# SDRAM.net
KiCad netlist of a schematic drawn in Altium Designer
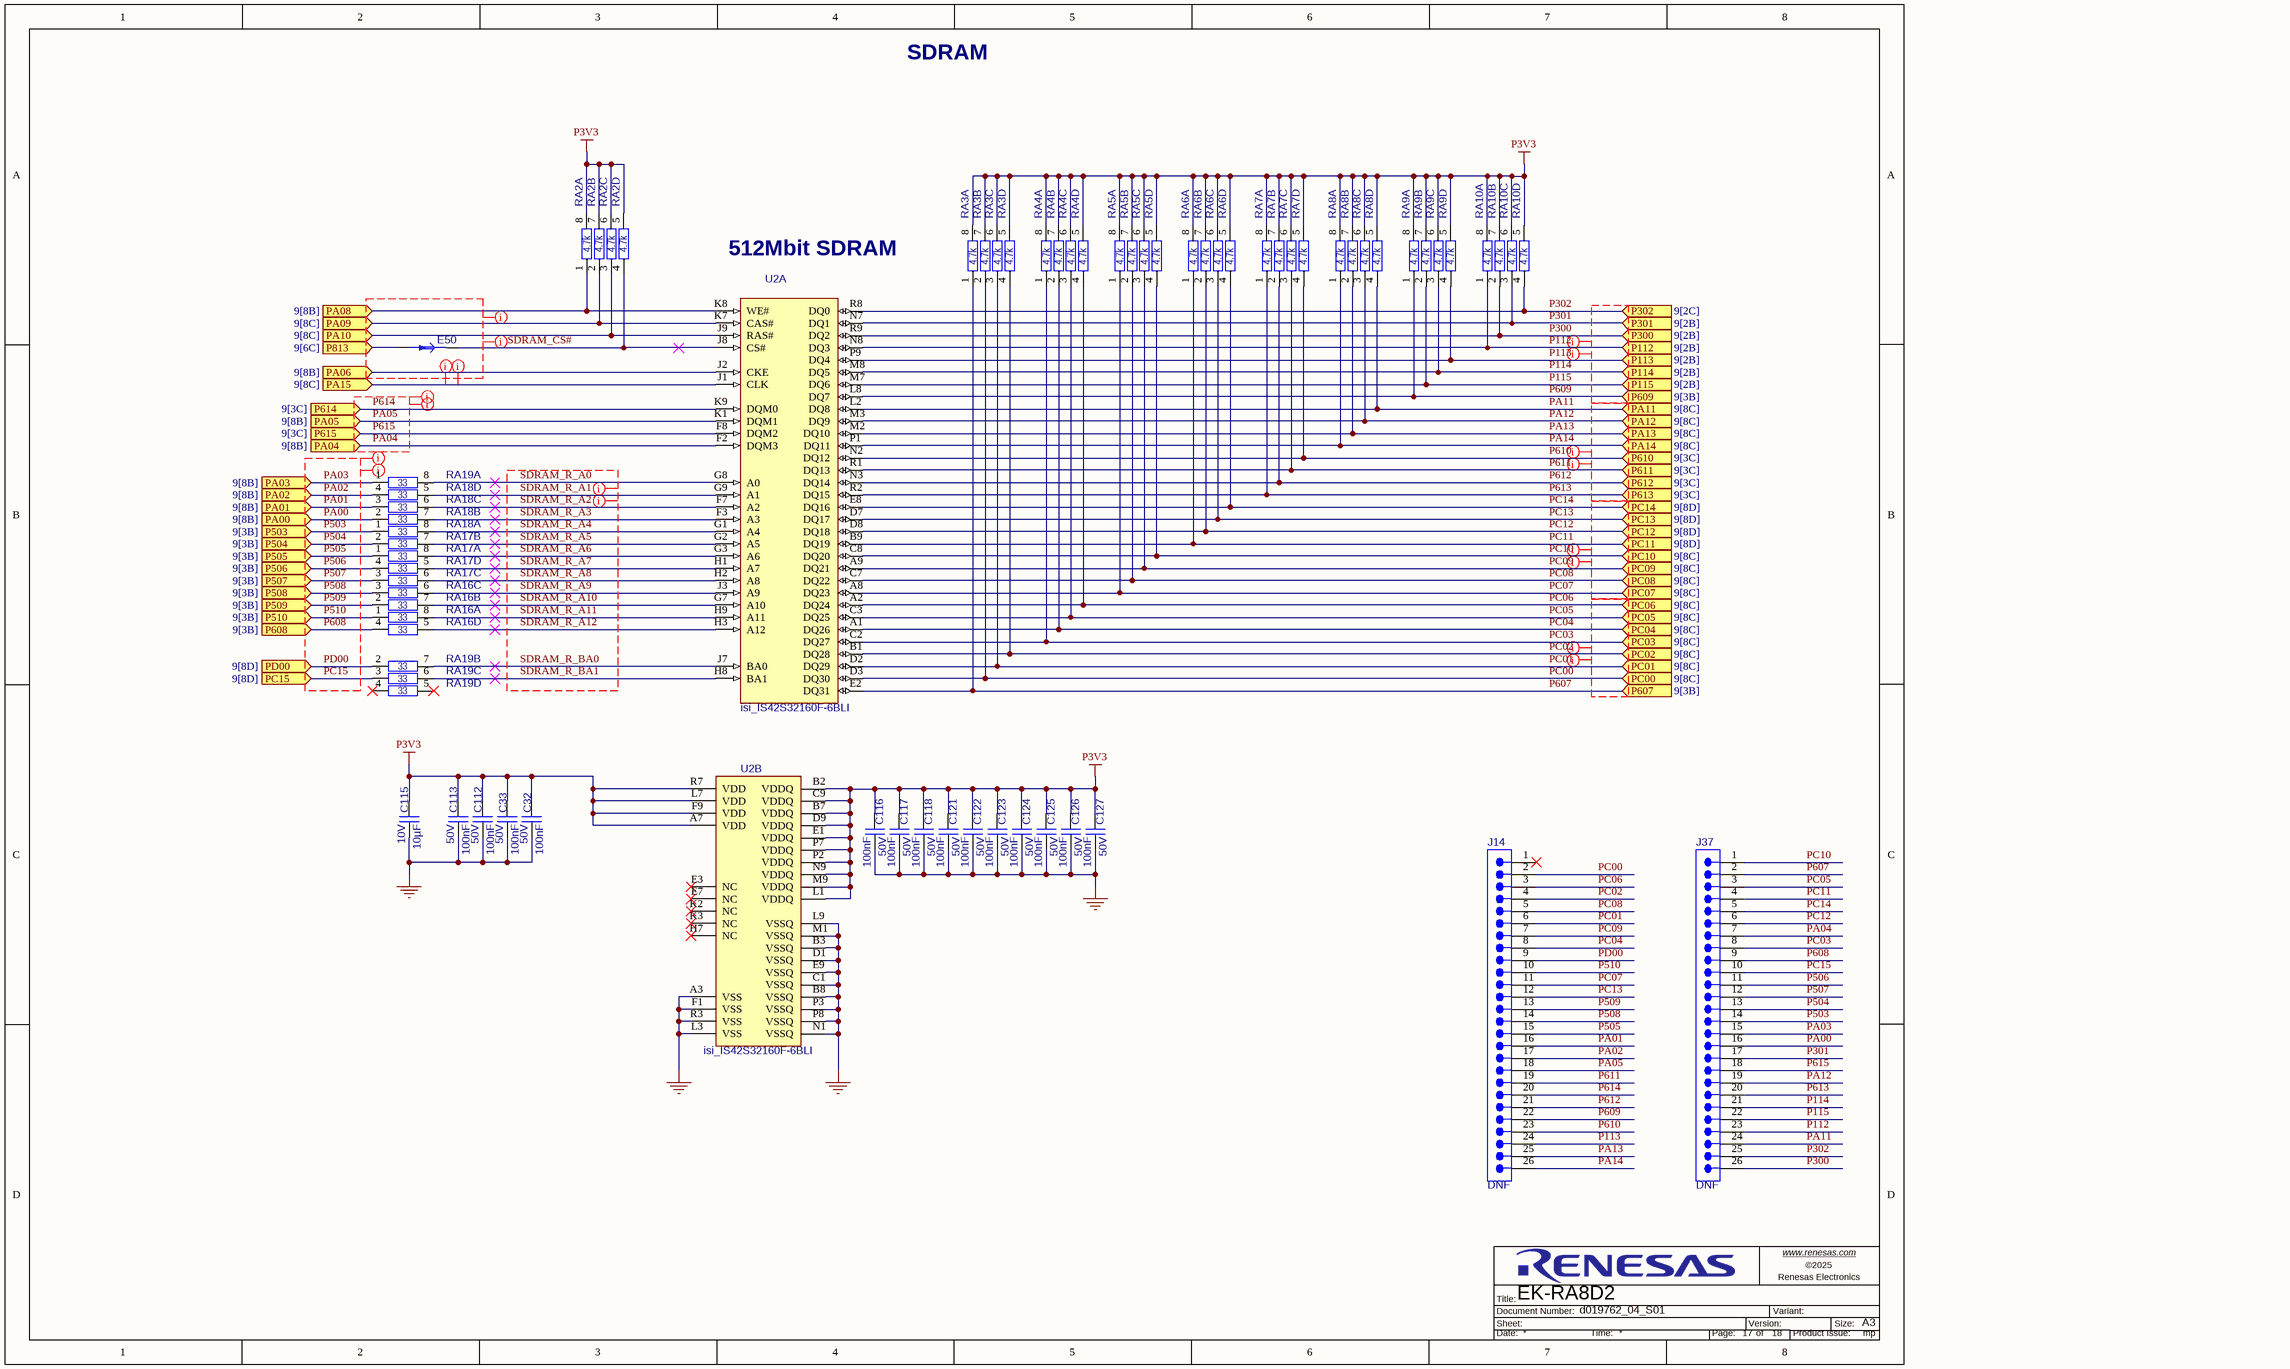
[diagram p0: SDRAM.SchDoc]

(export (version "E")
  (design (tool "Eeschema 10.0.6"))
  (components
    (comp (ref "C32")
      (value "100nF")
      (footprint "C_EIA0402_0p55")
      (description "Capacitor,EIA0402,100n,50V,X7R")
      (fields
        (field (name "TOLERANCE") "10%")
        (field (name "OPERATING VOLTAGE MAX") "50V")
        (field (name "Comment") "Capacitor")
      )
      (libsource (lib "ek-ra8d2_mp - Customer") (part "Capacitor"))
    )
    (comp (ref "C33")
      (value "100nF")
      (footprint "C_EIA0402_0p55")
      (description "Capacitor,EIA0402,100n,50V,X7R")
      (fields
        (field (name "TOLERANCE") "10%")
        (field (name "OPERATING VOLTAGE MAX") "50V")
        (field (name "Comment") "Capacitor")
      )
      (libsource (lib "ek-ra8d2_mp - Customer") (part "Capacitor"))
    )
    (comp (ref "C112")
      (value "100nF")
      (footprint "C_EIA0402_0p55")
      (description "Capacitor,EIA0402,100n,50V,X7R")
      (fields
        (field (name "TOLERANCE") "10%")
        (field (name "OPERATING VOLTAGE MAX") "50V")
        (field (name "Comment") "Capacitor")
      )
      (libsource (lib "ek-ra8d2_mp - Customer") (part "Capacitor"))
    )
    (comp (ref "C113")
      (value "100nF")
      (footprint "C_EIA0402_0p55")
      (description "Capacitor,EIA0402,100n,50V,X7R")
      (fields
        (field (name "TOLERANCE") "10%")
        (field (name "OPERATING VOLTAGE MAX") "50V")
        (field (name "Comment") "Capacitor")
      )
      (libsource (lib "ek-ra8d2_mp - Customer") (part "Capacitor"))
    )
    (comp (ref "C115")
      (value "10µF")
      (footprint "C_EIA0402_0p7")
      (description "Capacitor,EIA0402,10u,10V,X5R")
      (fields
        (field (name "TOLERANCE") "20%")
        (field (name "OPERATING VOLTAGE MAX") "10V")
        (field (name "Comment") "Capacitor")
      )
      (libsource (lib "ek-ra8d2_mp - Customer") (part "Capacitor"))
    )
    (comp (ref "C116")
      (value "100nF")
      (footprint "C_EIA0402_0p55")
      (description "Capacitor,EIA0402,100n,50V,X7R")
      (fields
        (field (name "TOLERANCE") "10%")
        (field (name "OPERATING VOLTAGE MAX") "50V")
        (field (name "Comment") "Capacitor")
      )
      (libsource (lib "ek-ra8d2_mp - Customer") (part "Capacitor"))
    )
    (comp (ref "C117")
      (value "100nF")
      (footprint "C_EIA0402_0p55")
      (description "Capacitor,EIA0402,100n,50V,X7R")
      (fields
        (field (name "TOLERANCE") "10%")
        (field (name "OPERATING VOLTAGE MAX") "50V")
        (field (name "Comment") "Capacitor")
      )
      (libsource (lib "ek-ra8d2_mp - Customer") (part "Capacitor"))
    )
    (comp (ref "C118")
      (value "100nF")
      (footprint "C_EIA0402_0p55")
      (description "Capacitor,EIA0402,100n,50V,X7R")
      (fields
        (field (name "TOLERANCE") "10%")
        (field (name "OPERATING VOLTAGE MAX") "50V")
        (field (name "Comment") "Capacitor")
      )
      (libsource (lib "ek-ra8d2_mp - Customer") (part "Capacitor"))
    )
    (comp (ref "C121")
      (value "100nF")
      (footprint "C_EIA0402_0p55")
      (description "Capacitor,EIA0402,100n,50V,X7R")
      (fields
        (field (name "TOLERANCE") "10%")
        (field (name "OPERATING VOLTAGE MAX") "50V")
        (field (name "Comment") "Capacitor")
      )
      (libsource (lib "ek-ra8d2_mp - Customer") (part "Capacitor"))
    )
    (comp (ref "C122")
      (value "100nF")
      (footprint "C_EIA0402_0p55")
      (description "Capacitor,EIA0402,100n,50V,X7R")
      (fields
        (field (name "TOLERANCE") "10%")
        (field (name "OPERATING VOLTAGE MAX") "50V")
        (field (name "Comment") "Capacitor")
      )
      (libsource (lib "ek-ra8d2_mp - Customer") (part "Capacitor"))
    )
    (comp (ref "C123")
      (value "100nF")
      (footprint "C_EIA0402_0p55")
      (description "Capacitor,EIA0402,100n,50V,X7R")
      (fields
        (field (name "TOLERANCE") "10%")
        (field (name "OPERATING VOLTAGE MAX") "50V")
        (field (name "Comment") "Capacitor")
      )
      (libsource (lib "ek-ra8d2_mp - Customer") (part "Capacitor"))
    )
    (comp (ref "C124")
      (value "100nF")
      (footprint "C_EIA0402_0p55")
      (description "Capacitor,EIA0402,100n,50V,X7R")
      (fields
        (field (name "TOLERANCE") "10%")
        (field (name "OPERATING VOLTAGE MAX") "50V")
        (field (name "Comment") "Capacitor")
      )
      (libsource (lib "ek-ra8d2_mp - Customer") (part "Capacitor"))
    )
    (comp (ref "C125")
      (value "100nF")
      (footprint "C_EIA0402_0p55")
      (description "Capacitor,EIA0402,100n,50V,X7R")
      (fields
        (field (name "TOLERANCE") "10%")
        (field (name "OPERATING VOLTAGE MAX") "50V")
        (field (name "Comment") "Capacitor")
      )
      (libsource (lib "ek-ra8d2_mp - Customer") (part "Capacitor"))
    )
    (comp (ref "C126")
      (value "100nF")
      (footprint "C_EIA0402_0p55")
      (description "Capacitor,EIA0402,100n,50V,X7R")
      (fields
        (field (name "TOLERANCE") "10%")
        (field (name "OPERATING VOLTAGE MAX") "50V")
        (field (name "Comment") "Capacitor")
      )
      (libsource (lib "ek-ra8d2_mp - Customer") (part "Capacitor"))
    )
    (comp (ref "C127")
      (value "100nF")
      (footprint "C_EIA0402_0p55")
      (description "Capacitor,EIA0402,100n,50V,X7R")
      (fields
        (field (name "TOLERANCE") "10%")
        (field (name "OPERATING VOLTAGE MAX") "50V")
        (field (name "Comment") "Capacitor")
      )
      (libsource (lib "ek-ra8d2_mp - Customer") (part "Capacitor"))
    )
    (comp (ref "E50")
      (value "TRACE_CUT_0805")
      (footprint "trace_cut_0805")
      (description "Trace Cut, SMD, 0805 size")
      (libsource (lib "ek-ra8d2_mp - Customer") (part "trace_cut"))
    )
    (comp (ref "J14")
      (value "NRPN132PAEN-RC")
      (footprint "sul_NRPN132PAEN-RC")
      (description "Header,26way,2row,vertical,2.00mm,THT")
      (fields (field (name "DNF") "DNF"))
      (libsource (lib "ek-ra8d2_mp - Customer") (part "CON_026"))
    )
    (comp (ref "J37")
      (value "NRPN132PAEN-RC")
      (footprint "sul_NRPN132PAEN-RC")
      (description "Header,26way,2row,vertical,2.00mm,THT")
      (fields (field (name "DNF") "DNF"))
      (libsource (lib "ek-ra8d2_mp - Customer") (part "CON_026"))
    )
    (comp (ref "RA2")
      (value "4.7k")
      (footprint "R_Array_EIA0804")
      (description "Resistor Network & Array,0804,4.7k,0.0625W")
      (fields (field (name "POWER") "62.5mW") (field (name "TOLERANCE") "1%"))
      (libsource (lib "") (part "Resistor_Array_1"))
    )
    (comp (ref "RA3")
      (value "4.7k")
      (footprint "R_Array_EIA0804")
      (description "Resistor Network & Array,0804,4.7k,0.0625W")
      (fields (field (name "POWER") "62.5mW") (field (name "TOLERANCE") "1%"))
      (libsource (lib "") (part "Resistor_Array_1"))
    )
    (comp (ref "RA4")
      (value "4.7k")
      (footprint "R_Array_EIA0804")
      (description "Resistor Network & Array,0804,4.7k,0.0625W")
      (fields (field (name "POWER") "62.5mW") (field (name "TOLERANCE") "1%"))
      (libsource (lib "") (part "Resistor_Array_1"))
    )
    (comp (ref "RA5")
      (value "4.7k")
      (footprint "R_Array_EIA0804")
      (description "Resistor Network & Array,0804,4.7k,0.0625W")
      (fields (field (name "POWER") "62.5mW") (field (name "TOLERANCE") "1%"))
      (libsource (lib "") (part "Resistor_Array_1"))
    )
    (comp (ref "RA6")
      (value "4.7k")
      (footprint "R_Array_EIA0804")
      (description "Resistor Network & Array,0804,4.7k,0.0625W")
      (fields (field (name "POWER") "62.5mW") (field (name "TOLERANCE") "1%"))
      (libsource (lib "") (part "Resistor_Array_1"))
    )
    (comp (ref "RA7")
      (value "4.7k")
      (footprint "R_Array_EIA0804")
      (description "Resistor Network & Array,0804,4.7k,0.0625W")
      (fields (field (name "POWER") "62.5mW") (field (name "TOLERANCE") "1%"))
      (libsource (lib "") (part "Resistor_Array_1"))
    )
    (comp (ref "RA8")
      (value "4.7k")
      (footprint "R_Array_EIA0804")
      (description "Resistor Network & Array,0804,4.7k,0.0625W")
      (fields (field (name "POWER") "62.5mW") (field (name "TOLERANCE") "1%"))
      (libsource (lib "") (part "Resistor_Array_1"))
    )
    (comp (ref "RA9")
      (value "4.7k")
      (footprint "R_Array_EIA0804")
      (description "Resistor Network & Array,0804,4.7k,0.0625W")
      (fields (field (name "POWER") "62.5mW") (field (name "TOLERANCE") "1%"))
      (libsource (lib "") (part "Resistor_Array_1"))
    )
    (comp (ref "RA10")
      (value "4.7k")
      (footprint "R_Array_EIA0804")
      (description "Resistor Network & Array,0804,4.7k,0.0625W")
      (fields (field (name "POWER") "62.5mW") (field (name "TOLERANCE") "1%"))
      (libsource (lib "") (part "Resistor_Array_1"))
    )
    (comp (ref "RA16")
      (value "33")
      (footprint "R_Array_EIA0804")
      (description "Resistor Network & Array,0804,33,0.0625W")
      (fields (field (name "POWER") "62.5mW") (field (name "TOLERANCE") "1%"))
      (libsource (lib "ek-ra8d2_mp - Customer") (part "Resistor_Array"))
    )
    (comp (ref "RA17")
      (value "33")
      (footprint "R_Array_EIA0804")
      (description "Resistor Network & Array,0804,33,0.0625W")
      (fields (field (name "POWER") "62.5mW") (field (name "TOLERANCE") "1%"))
      (libsource (lib "ek-ra8d2_mp - Customer") (part "Resistor_Array"))
    )
    (comp (ref "RA18")
      (value "33")
      (footprint "R_Array_EIA0804")
      (description "Resistor Network & Array,0804,33,0.0625W")
      (fields (field (name "POWER") "62.5mW") (field (name "TOLERANCE") "1%"))
      (libsource (lib "ek-ra8d2_mp - Customer") (part "Resistor_Array"))
    )
    (comp (ref "RA19")
      (value "33")
      (footprint "R_Array_EIA0804")
      (description "Resistor Network & Array,0804,33,0.0625W")
      (fields (field (name "POWER") "62.5mW") (field (name "TOLERANCE") "1%"))
      (libsource (lib "ek-ra8d2_mp - Customer") (part "Resistor_Array"))
    )
    (comp (ref "U2")
      (value "isi_IS42S32160F-6BLI")
      (footprint "isi_TF-BGA-90_8x13mm")
      (description "512Mb Synchronous DRAM, 16MX32, 5.4ns, CMOS, TF-BGA90")
      (libsource (lib "ek-ra8d2_mp - Customer") (part "isi_IS42S32160F-6BLI"))
    )
  )
  (nets
    (net (code "2") (name "/P112") (class "Default")
      (node (ref "J37") (pin "23") (pinfunction "23_23") (pintype "passive"))
      (node (ref "RA10") (pin "1") (pinfunction "1_1") (pintype "passive"))
      (node (ref "U2") (pin "N8") (pinfunction "DQ3_N8") (pintype "bidirectional"))
    )
    (net (code "3") (name "/P113") (class "Default")
      (node (ref "J14") (pin "24") (pinfunction "24_24") (pintype "passive"))
      (node (ref "RA9") (pin "4") (pinfunction "4_4") (pintype "passive"))
      (node (ref "U2") (pin "P9") (pinfunction "DQ4_P9") (pintype "bidirectional"))
    )
    (net (code "4") (name "/P114") (class "Default")
      (node (ref "J37") (pin "21") (pinfunction "21_21") (pintype "passive"))
      (node (ref "RA9") (pin "3") (pinfunction "3_3") (pintype "passive"))
      (node (ref "U2") (pin "M8") (pinfunction "DQ5_M8") (pintype "bidirectional"))
    )
    (net (code "5") (name "/P115") (class "Default")
      (node (ref "J37") (pin "22") (pinfunction "22_22") (pintype "passive"))
      (node (ref "RA9") (pin "2") (pinfunction "2_2") (pintype "passive"))
      (node (ref "U2") (pin "M7") (pinfunction "DQ6_M7") (pintype "bidirectional"))
    )
    (net (code "6") (name "/P300") (class "Default")
      (node (ref "J37") (pin "26") (pinfunction "26_26") (pintype "passive"))
      (node (ref "RA10") (pin "2") (pinfunction "2_2") (pintype "passive"))
      (node (ref "U2") (pin "R9") (pinfunction "DQ2_R9") (pintype "bidirectional"))
    )
    (net (code "7") (name "/P301") (class "Default")
      (node (ref "J37") (pin "17") (pinfunction "17_17") (pintype "passive"))
      (node (ref "RA10") (pin "3") (pinfunction "3_3") (pintype "passive"))
      (node (ref "U2") (pin "N7") (pinfunction "DQ1_N7") (pintype "bidirectional"))
    )
    (net (code "8") (name "/P302") (class "Default")
      (node (ref "J37") (pin "25") (pinfunction "25_25") (pintype "passive"))
      (node (ref "RA10") (pin "4") (pinfunction "4_4") (pintype "passive"))
      (node (ref "U2") (pin "R8") (pinfunction "DQ0_R8") (pintype "bidirectional"))
    )
    (net (code "9") (name "/P503") (class "Default")
      (node (ref "J37") (pin "14") (pinfunction "14_14") (pintype "passive"))
      (node (ref "RA18") (pin "1") (pinfunction "1_1") (pintype "passive"))
    )
    (net (code "10") (name "/P504") (class "Default")
      (node (ref "J37") (pin "13") (pinfunction "13_13") (pintype "passive"))
      (node (ref "RA17") (pin "2") (pinfunction "2_2") (pintype "passive"))
    )
    (net (code "11") (name "/P505") (class "Default")
      (node (ref "J14") (pin "15") (pinfunction "15_15") (pintype "passive"))
      (node (ref "RA17") (pin "1") (pinfunction "1_1") (pintype "passive"))
    )
    (net (code "12") (name "/P506") (class "Default")
      (node (ref "J37") (pin "11") (pinfunction "11_11") (pintype "passive"))
      (node (ref "RA17") (pin "4") (pinfunction "4_4") (pintype "passive"))
    )
    (net (code "13") (name "/P507") (class "Default")
      (node (ref "J37") (pin "12") (pinfunction "12_12") (pintype "passive"))
      (node (ref "RA17") (pin "3") (pinfunction "3_3") (pintype "passive"))
    )
    (net (code "14") (name "/P508") (class "Default")
      (node (ref "J14") (pin "14") (pinfunction "14_14") (pintype "passive"))
      (node (ref "RA16") (pin "3") (pinfunction "3_3") (pintype "passive"))
    )
    (net (code "15") (name "/P509") (class "Default")
      (node (ref "J14") (pin "13") (pinfunction "13_13") (pintype "passive"))
      (node (ref "RA16") (pin "2") (pinfunction "2_2") (pintype "passive"))
    )
    (net (code "16") (name "/P510") (class "Default")
      (node (ref "J14") (pin "10") (pinfunction "10_10") (pintype "passive"))
      (node (ref "RA16") (pin "1") (pinfunction "1_1") (pintype "passive"))
    )
    (net (code "17") (name "/P607") (class "Default")
      (node (ref "J37") (pin "2") (pinfunction "2_2") (pintype "passive"))
      (node (ref "RA3") (pin "1") (pinfunction "1_1") (pintype "passive"))
      (node (ref "U2") (pin "E2") (pinfunction "DQ31_E2") (pintype "bidirectional"))
    )
    (net (code "18") (name "/P608") (class "Default")
      (node (ref "J37") (pin "9") (pinfunction "9_9") (pintype "passive"))
      (node (ref "RA16") (pin "4") (pinfunction "4_4") (pintype "passive"))
    )
    (net (code "19") (name "/P609") (class "Default")
      (node (ref "J14") (pin "22") (pinfunction "22_22") (pintype "passive"))
      (node (ref "RA9") (pin "1") (pinfunction "1_1") (pintype "passive"))
      (node (ref "U2") (pin "L8") (pinfunction "DQ7_L8") (pintype "bidirectional"))
    )
    (net (code "20") (name "/P610") (class "Default")
      (node (ref "J14") (pin "23") (pinfunction "23_23") (pintype "passive"))
      (node (ref "RA7") (pin "4") (pinfunction "4_4") (pintype "passive"))
      (node (ref "U2") (pin "N2") (pinfunction "DQ12_N2") (pintype "bidirectional"))
    )
    (net (code "21") (name "/P611") (class "Default")
      (node (ref "J14") (pin "19") (pinfunction "19_19") (pintype "passive"))
      (node (ref "RA7") (pin "3") (pinfunction "3_3") (pintype "passive"))
      (node (ref "U2") (pin "R1") (pinfunction "DQ13_R1") (pintype "bidirectional"))
    )
    (net (code "22") (name "/P612") (class "Default")
      (node (ref "J14") (pin "21") (pinfunction "21_21") (pintype "passive"))
      (node (ref "RA7") (pin "2") (pinfunction "2_2") (pintype "passive"))
      (node (ref "U2") (pin "N3") (pinfunction "DQ14_N3") (pintype "bidirectional"))
    )
    (net (code "23") (name "/P613") (class "Default")
      (node (ref "J37") (pin "20") (pinfunction "20_20") (pintype "passive"))
      (node (ref "RA7") (pin "1") (pinfunction "1_1") (pintype "passive"))
      (node (ref "U2") (pin "R2") (pinfunction "DQ15_R2") (pintype "bidirectional"))
    )
    (net (code "24") (name "/P614") (class "Default")
      (node (ref "J14") (pin "20") (pinfunction "20_20") (pintype "passive"))
      (node (ref "U2") (pin "K9") (pinfunction "DQM0_K9") (pintype "input"))
    )
    (net (code "25") (name "/P615") (class "Default")
      (node (ref "J37") (pin "18") (pinfunction "18_18") (pintype "passive"))
      (node (ref "U2") (pin "F8") (pinfunction "DQM2_F8") (pintype "input"))
    )
    (net (code "26") (name "/P813") (class "Default")
      (node (ref "E50") (pin "2") (pinfunction "2_2") (pintype "passive"))
    )
    (net (code "27") (name "/PA00") (class "Default")
      (node (ref "J37") (pin "16") (pinfunction "16_16") (pintype "passive"))
      (node (ref "RA18") (pin "2") (pinfunction "2_2") (pintype "passive"))
    )
    (net (code "28") (name "/PA01") (class "Default")
      (node (ref "J14") (pin "16") (pinfunction "16_16") (pintype "passive"))
      (node (ref "RA18") (pin "3") (pinfunction "3_3") (pintype "passive"))
    )
    (net (code "29") (name "/PA02") (class "Default")
      (node (ref "J14") (pin "17") (pinfunction "17_17") (pintype "passive"))
      (node (ref "RA18") (pin "4") (pinfunction "4_4") (pintype "passive"))
    )
    (net (code "30") (name "/PA03") (class "Default")
      (node (ref "J37") (pin "15") (pinfunction "15_15") (pintype "passive"))
      (node (ref "RA19") (pin "1") (pinfunction "1_1") (pintype "passive"))
    )
    (net (code "31") (name "/PA04") (class "Default")
      (node (ref "J37") (pin "7") (pinfunction "7_7") (pintype "passive"))
      (node (ref "U2") (pin "F2") (pinfunction "DQM3_F2") (pintype "input"))
    )
    (net (code "32") (name "/PA05") (class "Default")
      (node (ref "J14") (pin "18") (pinfunction "18_18") (pintype "passive"))
      (node (ref "U2") (pin "K1") (pinfunction "DQM1_K1") (pintype "input"))
    )
    (net (code "33") (name "/PA06") (class "Default")
      (node (ref "U2") (pin "J2") (pinfunction "CKE_J2") (pintype "input"))
    )
    (net (code "34") (name "/PA08") (class "Default")
      (node (ref "RA2") (pin "1") (pinfunction "1_1") (pintype "passive"))
      (node (ref "U2") (pin "K8") (pinfunction "WE#_K8") (pintype "input"))
    )
    (net (code "35") (name "/PA09") (class "Default")
      (node (ref "RA2") (pin "2") (pinfunction "2_2") (pintype "passive"))
      (node (ref "U2") (pin "K7") (pinfunction "CAS#_K7") (pintype "input"))
    )
    (net (code "36") (name "/PA10") (class "Default")
      (node (ref "RA2") (pin "3") (pinfunction "3_3") (pintype "passive"))
      (node (ref "U2") (pin "J9") (pinfunction "RAS#_J9") (pintype "input"))
    )
    (net (code "37") (name "/PA11") (class "Default")
      (node (ref "J37") (pin "24") (pinfunction "24_24") (pintype "passive"))
      (node (ref "RA8") (pin "4") (pinfunction "4_4") (pintype "passive"))
      (node (ref "U2") (pin "L2") (pinfunction "DQ8_L2") (pintype "bidirectional"))
    )
    (net (code "38") (name "/PA12") (class "Default")
      (node (ref "J37") (pin "19") (pinfunction "19_19") (pintype "passive"))
      (node (ref "RA8") (pin "3") (pinfunction "3_3") (pintype "passive"))
      (node (ref "U2") (pin "M3") (pinfunction "DQ9_M3") (pintype "bidirectional"))
    )
    (net (code "39") (name "/PA13") (class "Default")
      (node (ref "J14") (pin "25") (pinfunction "25_25") (pintype "passive"))
      (node (ref "RA8") (pin "2") (pinfunction "2_2") (pintype "passive"))
      (node (ref "U2") (pin "M2") (pinfunction "DQ10_M2") (pintype "bidirectional"))
    )
    (net (code "40") (name "/PA14") (class "Default")
      (node (ref "J14") (pin "26") (pinfunction "26_26") (pintype "passive"))
      (node (ref "RA8") (pin "1") (pinfunction "1_1") (pintype "passive"))
      (node (ref "U2") (pin "P1") (pinfunction "DQ11_P1") (pintype "bidirectional"))
    )
    (net (code "41") (name "/PA15") (class "Default")
      (node (ref "U2") (pin "J1") (pinfunction "CLK_J1") (pintype "input"))
    )
    (net (code "42") (name "/PC00") (class "Default")
      (node (ref "J14") (pin "2") (pinfunction "2_2") (pintype "passive"))
      (node (ref "RA3") (pin "2") (pinfunction "2_2") (pintype "passive"))
      (node (ref "U2") (pin "D3") (pinfunction "DQ30_D3") (pintype "bidirectional"))
    )
    (net (code "43") (name "/PC01") (class "Default")
      (node (ref "J14") (pin "6") (pinfunction "6_6") (pintype "passive"))
      (node (ref "RA3") (pin "3") (pinfunction "3_3") (pintype "passive"))
      (node (ref "U2") (pin "D2") (pinfunction "DQ29_D2") (pintype "bidirectional"))
    )
    (net (code "44") (name "/PC02") (class "Default")
      (node (ref "J14") (pin "4") (pinfunction "4_4") (pintype "passive"))
      (node (ref "RA3") (pin "4") (pinfunction "4_4") (pintype "passive"))
      (node (ref "U2") (pin "B1") (pinfunction "DQ28_B1") (pintype "bidirectional"))
    )
    (net (code "45") (name "/PC03") (class "Default")
      (node (ref "J37") (pin "8") (pinfunction "8_8") (pintype "passive"))
      (node (ref "RA4") (pin "1") (pinfunction "1_1") (pintype "passive"))
      (node (ref "U2") (pin "C2") (pinfunction "DQ27_C2") (pintype "bidirectional"))
    )
    (net (code "46") (name "/PC04") (class "Default")
      (node (ref "J14") (pin "8") (pinfunction "8_8") (pintype "passive"))
      (node (ref "RA4") (pin "2") (pinfunction "2_2") (pintype "passive"))
      (node (ref "U2") (pin "A1") (pinfunction "DQ26_A1") (pintype "bidirectional"))
    )
    (net (code "47") (name "/PC05") (class "Default")
      (node (ref "J37") (pin "3") (pinfunction "3_3") (pintype "passive"))
      (node (ref "RA4") (pin "3") (pinfunction "3_3") (pintype "passive"))
      (node (ref "U2") (pin "C3") (pinfunction "DQ25_C3") (pintype "bidirectional"))
    )
    (net (code "48") (name "/PC06") (class "Default")
      (node (ref "J14") (pin "3") (pinfunction "3_3") (pintype "passive"))
      (node (ref "RA4") (pin "4") (pinfunction "4_4") (pintype "passive"))
      (node (ref "U2") (pin "A2") (pinfunction "DQ24_A2") (pintype "bidirectional"))
    )
    (net (code "49") (name "/PC07") (class "Default")
      (node (ref "J14") (pin "11") (pinfunction "11_11") (pintype "passive"))
      (node (ref "RA5") (pin "1") (pinfunction "1_1") (pintype "passive"))
      (node (ref "U2") (pin "A8") (pinfunction "DQ23_A8") (pintype "bidirectional"))
    )
    (net (code "50") (name "/PC08") (class "Default")
      (node (ref "J14") (pin "5") (pinfunction "5_5") (pintype "passive"))
      (node (ref "RA5") (pin "2") (pinfunction "2_2") (pintype "passive"))
      (node (ref "U2") (pin "C7") (pinfunction "DQ22_C7") (pintype "bidirectional"))
    )
    (net (code "51") (name "/PC09") (class "Default")
      (node (ref "J14") (pin "7") (pinfunction "7_7") (pintype "passive"))
      (node (ref "RA5") (pin "3") (pinfunction "3_3") (pintype "passive"))
      (node (ref "U2") (pin "A9") (pinfunction "DQ21_A9") (pintype "bidirectional"))
    )
    (net (code "52") (name "/PC10") (class "Default")
      (node (ref "J37") (pin "1") (pinfunction "1_1") (pintype "passive"))
      (node (ref "RA5") (pin "4") (pinfunction "4_4") (pintype "passive"))
      (node (ref "U2") (pin "C8") (pinfunction "DQ20_C8") (pintype "bidirectional"))
    )
    (net (code "53") (name "/PC11") (class "Default")
      (node (ref "J37") (pin "4") (pinfunction "4_4") (pintype "passive"))
      (node (ref "RA6") (pin "1") (pinfunction "1_1") (pintype "passive"))
      (node (ref "U2") (pin "B9") (pinfunction "DQ19_B9") (pintype "bidirectional"))
    )
    (net (code "54") (name "/PC12") (class "Default")
      (node (ref "J37") (pin "6") (pinfunction "6_6") (pintype "passive"))
      (node (ref "RA6") (pin "2") (pinfunction "2_2") (pintype "passive"))
      (node (ref "U2") (pin "D8") (pinfunction "DQ18_D8") (pintype "bidirectional"))
    )
    (net (code "55") (name "/PC13") (class "Default")
      (node (ref "J14") (pin "12") (pinfunction "12_12") (pintype "passive"))
      (node (ref "RA6") (pin "3") (pinfunction "3_3") (pintype "passive"))
      (node (ref "U2") (pin "D7") (pinfunction "DQ17_D7") (pintype "bidirectional"))
    )
    (net (code "56") (name "/PC14") (class "Default")
      (node (ref "J37") (pin "5") (pinfunction "5_5") (pintype "passive"))
      (node (ref "RA6") (pin "4") (pinfunction "4_4") (pintype "passive"))
      (node (ref "U2") (pin "E8") (pinfunction "DQ16_E8") (pintype "bidirectional"))
    )
    (net (code "57") (name "/PC15") (class "Default")
      (node (ref "J37") (pin "10") (pinfunction "10_10") (pintype "passive"))
      (node (ref "RA19") (pin "3") (pinfunction "3_3") (pintype "passive"))
    )
    (net (code "58") (name "/PD00") (class "Default")
      (node (ref "J14") (pin "9") (pinfunction "9_9") (pintype "passive"))
      (node (ref "RA19") (pin "2") (pinfunction "2_2") (pintype "passive"))
    )
    (net (code "59") (name "/SDRAM_CS#") (class "Default")
      (node (ref "E50") (pin "1") (pinfunction "1_1") (pintype "passive"))
      (node (ref "RA2") (pin "4") (pinfunction "4_4") (pintype "passive"))
      (node (ref "U2") (pin "J8") (pinfunction "CS#_J8") (pintype "input"))
    )
    (net (code "60") (name "/SDRAM_R_A0") (class "Default")
      (node (ref "RA19") (pin "8") (pinfunction "8_8") (pintype "passive"))
      (node (ref "U2") (pin "G8") (pinfunction "A0_G8") (pintype "input"))
    )
    (net (code "61") (name "/SDRAM_R_A1") (class "Default")
      (node (ref "RA18") (pin "5") (pinfunction "5_5") (pintype "passive"))
      (node (ref "U2") (pin "G9") (pinfunction "A1_G9") (pintype "input"))
    )
    (net (code "62") (name "/SDRAM_R_A2") (class "Default")
      (node (ref "RA18") (pin "6") (pinfunction "6_6") (pintype "passive"))
      (node (ref "U2") (pin "F7") (pinfunction "A2_F7") (pintype "input"))
    )
    (net (code "63") (name "/SDRAM_R_A3") (class "Default")
      (node (ref "RA18") (pin "7") (pinfunction "7_7") (pintype "passive"))
      (node (ref "U2") (pin "F3") (pinfunction "A3_F3") (pintype "input"))
    )
    (net (code "64") (name "/SDRAM_R_A4") (class "Default")
      (node (ref "RA18") (pin "8") (pinfunction "8_8") (pintype "passive"))
      (node (ref "U2") (pin "G1") (pinfunction "A4_G1") (pintype "input"))
    )
    (net (code "65") (name "/SDRAM_R_A5") (class "Default")
      (node (ref "RA17") (pin "7") (pinfunction "7_7") (pintype "passive"))
      (node (ref "U2") (pin "G2") (pinfunction "A5_G2") (pintype "input"))
    )
    (net (code "66") (name "/SDRAM_R_A6") (class "Default")
      (node (ref "RA17") (pin "8") (pinfunction "8_8") (pintype "passive"))
      (node (ref "U2") (pin "G3") (pinfunction "A6_G3") (pintype "input"))
    )
    (net (code "67") (name "/SDRAM_R_A7") (class "Default")
      (node (ref "RA17") (pin "5") (pinfunction "5_5") (pintype "passive"))
      (node (ref "U2") (pin "H1") (pinfunction "A7_H1") (pintype "input"))
    )
    (net (code "68") (name "/SDRAM_R_A8") (class "Default")
      (node (ref "RA17") (pin "6") (pinfunction "6_6") (pintype "passive"))
      (node (ref "U2") (pin "H2") (pinfunction "A8_H2") (pintype "input"))
    )
    (net (code "69") (name "/SDRAM_R_A9") (class "Default")
      (node (ref "RA16") (pin "6") (pinfunction "6_6") (pintype "passive"))
      (node (ref "U2") (pin "J3") (pinfunction "A9_J3") (pintype "input"))
    )
    (net (code "70") (name "/SDRAM_R_A10") (class "Default")
      (node (ref "RA16") (pin "7") (pinfunction "7_7") (pintype "passive"))
      (node (ref "U2") (pin "G7") (pinfunction "A10_G7") (pintype "input"))
    )
    (net (code "71") (name "/SDRAM_R_A11") (class "Default")
      (node (ref "RA16") (pin "8") (pinfunction "8_8") (pintype "passive"))
      (node (ref "U2") (pin "H9") (pinfunction "A11_H9") (pintype "input"))
    )
    (net (code "72") (name "/SDRAM_R_A12") (class "Default")
      (node (ref "RA16") (pin "5") (pinfunction "5_5") (pintype "passive"))
      (node (ref "U2") (pin "H3") (pinfunction "A12_H3") (pintype "input"))
    )
    (net (code "73") (name "/SDRAM_R_BA0") (class "Default")
      (node (ref "RA19") (pin "7") (pinfunction "7_7") (pintype "passive"))
      (node (ref "U2") (pin "J7") (pinfunction "BA0_J7") (pintype "input"))
    )
    (net (code "74") (name "/SDRAM_R_BA1") (class "Default")
      (node (ref "RA19") (pin "6") (pinfunction "6_6") (pintype "passive"))
      (node (ref "U2") (pin "H8") (pinfunction "BA1_H8") (pintype "input"))
    )
    (net (code "75") (name "GND") (class "Default")
      (node (ref "C112") (pin "2") (pinfunction "2_2") (pintype "passive"))
      (node (ref "C113") (pin "2") (pinfunction "2_2") (pintype "passive"))
      (node (ref "C115") (pin "2") (pinfunction "2_2") (pintype "passive"))
      (node (ref "C116") (pin "2") (pinfunction "2_2") (pintype "passive"))
      (node (ref "C117") (pin "2") (pinfunction "2_2") (pintype "passive"))
      (node (ref "C118") (pin "2") (pinfunction "2_2") (pintype "passive"))
      (node (ref "C121") (pin "2") (pinfunction "2_2") (pintype "passive"))
      (node (ref "C122") (pin "2") (pinfunction "2_2") (pintype "passive"))
      (node (ref "C123") (pin "2") (pinfunction "2_2") (pintype "passive"))
      (node (ref "C124") (pin "2") (pinfunction "2_2") (pintype "passive"))
      (node (ref "C125") (pin "2") (pinfunction "2_2") (pintype "passive"))
      (node (ref "C126") (pin "2") (pinfunction "2_2") (pintype "passive"))
      (node (ref "C127") (pin "2") (pinfunction "2_2") (pintype "passive"))
      (node (ref "C32") (pin "2") (pinfunction "2_2") (pintype "passive"))
      (node (ref "C33") (pin "2") (pinfunction "2_2") (pintype "passive"))
      (node (ref "U2") (pin "A3") (pinfunction "VSS_A3") (pintype "power_in"))
      (node (ref "U2") (pin "B3") (pinfunction "VSSQ_B3") (pintype "power_in"))
      (node (ref "U2") (pin "B8") (pinfunction "VSSQ_B8") (pintype "power_in"))
      (node (ref "U2") (pin "C1") (pinfunction "VSSQ_C1") (pintype "power_in"))
      (node (ref "U2") (pin "D1") (pinfunction "VSSQ_D1") (pintype "power_in"))
      (node (ref "U2") (pin "E9") (pinfunction "VSSQ_E9") (pintype "power_in"))
      (node (ref "U2") (pin "F1") (pinfunction "VSS_F1") (pintype "power_in"))
      (node (ref "U2") (pin "L3") (pinfunction "VSS_L3") (pintype "power_in"))
      (node (ref "U2") (pin "L9") (pinfunction "VSSQ_L9") (pintype "power_in"))
      (node (ref "U2") (pin "M1") (pinfunction "VSSQ_M1") (pintype "power_in"))
      (node (ref "U2") (pin "N1") (pinfunction "VSSQ_N1") (pintype "power_in"))
      (node (ref "U2") (pin "P3") (pinfunction "VSSQ_P3") (pintype "power_in"))
      (node (ref "U2") (pin "P8") (pinfunction "VSSQ_P8") (pintype "power_in"))
      (node (ref "U2") (pin "R3") (pinfunction "VSS_R3") (pintype "power_in"))
    )
    (net (code "76") (name "P3V3") (class "Default")
      (node (ref "C112") (pin "1") (pinfunction "1_1") (pintype "passive"))
      (node (ref "C113") (pin "1") (pinfunction "1_1") (pintype "passive"))
      (node (ref "C115") (pin "1") (pinfunction "1_1") (pintype "passive"))
      (node (ref "C116") (pin "1") (pinfunction "1_1") (pintype "passive"))
      (node (ref "C117") (pin "1") (pinfunction "1_1") (pintype "passive"))
      (node (ref "C118") (pin "1") (pinfunction "1_1") (pintype "passive"))
      (node (ref "C121") (pin "1") (pinfunction "1_1") (pintype "passive"))
      (node (ref "C122") (pin "1") (pinfunction "1_1") (pintype "passive"))
      (node (ref "C123") (pin "1") (pinfunction "1_1") (pintype "passive"))
      (node (ref "C124") (pin "1") (pinfunction "1_1") (pintype "passive"))
      (node (ref "C125") (pin "1") (pinfunction "1_1") (pintype "passive"))
      (node (ref "C126") (pin "1") (pinfunction "1_1") (pintype "passive"))
      (node (ref "C127") (pin "1") (pinfunction "1_1") (pintype "passive"))
      (node (ref "C32") (pin "1") (pinfunction "1_1") (pintype "passive"))
      (node (ref "C33") (pin "1") (pinfunction "1_1") (pintype "passive"))
      (node (ref "RA10") (pin "5") (pinfunction "5_5") (pintype "passive"))
      (node (ref "RA10") (pin "6") (pinfunction "6_6") (pintype "passive"))
      (node (ref "RA10") (pin "7") (pinfunction "7_7") (pintype "passive"))
      (node (ref "RA10") (pin "8") (pinfunction "8_8") (pintype "passive"))
      (node (ref "RA2") (pin "5") (pinfunction "5_5") (pintype "passive"))
      (node (ref "RA2") (pin "6") (pinfunction "6_6") (pintype "passive"))
      (node (ref "RA2") (pin "7") (pinfunction "7_7") (pintype "passive"))
      (node (ref "RA2") (pin "8") (pinfunction "8_8") (pintype "passive"))
      (node (ref "RA3") (pin "5") (pinfunction "5_5") (pintype "passive"))
      (node (ref "RA3") (pin "6") (pinfunction "6_6") (pintype "passive"))
      (node (ref "RA3") (pin "7") (pinfunction "7_7") (pintype "passive"))
      (node (ref "RA3") (pin "8") (pinfunction "8_8") (pintype "passive"))
      (node (ref "RA4") (pin "5") (pinfunction "5_5") (pintype "passive"))
      (node (ref "RA4") (pin "6") (pinfunction "6_6") (pintype "passive"))
      (node (ref "RA4") (pin "7") (pinfunction "7_7") (pintype "passive"))
      (node (ref "RA4") (pin "8") (pinfunction "8_8") (pintype "passive"))
      (node (ref "RA5") (pin "5") (pinfunction "5_5") (pintype "passive"))
      (node (ref "RA5") (pin "6") (pinfunction "6_6") (pintype "passive"))
      (node (ref "RA5") (pin "7") (pinfunction "7_7") (pintype "passive"))
      (node (ref "RA5") (pin "8") (pinfunction "8_8") (pintype "passive"))
      (node (ref "RA6") (pin "5") (pinfunction "5_5") (pintype "passive"))
      (node (ref "RA6") (pin "6") (pinfunction "6_6") (pintype "passive"))
      (node (ref "RA6") (pin "7") (pinfunction "7_7") (pintype "passive"))
      (node (ref "RA6") (pin "8") (pinfunction "8_8") (pintype "passive"))
      (node (ref "RA7") (pin "5") (pinfunction "5_5") (pintype "passive"))
      (node (ref "RA7") (pin "6") (pinfunction "6_6") (pintype "passive"))
      (node (ref "RA7") (pin "7") (pinfunction "7_7") (pintype "passive"))
      (node (ref "RA7") (pin "8") (pinfunction "8_8") (pintype "passive"))
      (node (ref "RA8") (pin "5") (pinfunction "5_5") (pintype "passive"))
      (node (ref "RA8") (pin "6") (pinfunction "6_6") (pintype "passive"))
      (node (ref "RA8") (pin "7") (pinfunction "7_7") (pintype "passive"))
      (node (ref "RA8") (pin "8") (pinfunction "8_8") (pintype "passive"))
      (node (ref "RA9") (pin "5") (pinfunction "5_5") (pintype "passive"))
      (node (ref "RA9") (pin "6") (pinfunction "6_6") (pintype "passive"))
      (node (ref "RA9") (pin "7") (pinfunction "7_7") (pintype "passive"))
      (node (ref "RA9") (pin "8") (pinfunction "8_8") (pintype "passive"))
      (node (ref "U2") (pin "A7") (pinfunction "VDD_A7") (pintype "power_in"))
      (node (ref "U2") (pin "B2") (pinfunction "VDDQ_B2") (pintype "power_in"))
      (node (ref "U2") (pin "B7") (pinfunction "VDDQ_B7") (pintype "power_in"))
      (node (ref "U2") (pin "C9") (pinfunction "VDDQ_C9") (pintype "power_in"))
      (node (ref "U2") (pin "D9") (pinfunction "VDDQ_D9") (pintype "power_in"))
      (node (ref "U2") (pin "E1") (pinfunction "VDDQ_E1") (pintype "power_in"))
      (node (ref "U2") (pin "F9") (pinfunction "VDD_F9") (pintype "power_in"))
      (node (ref "U2") (pin "L1") (pinfunction "VDDQ_L1") (pintype "power_in"))
      (node (ref "U2") (pin "L7") (pinfunction "VDD_L7") (pintype "power_in"))
      (node (ref "U2") (pin "M9") (pinfunction "VDDQ_M9") (pintype "power_in"))
      (node (ref "U2") (pin "N9") (pinfunction "VDDQ_N9") (pintype "power_in"))
      (node (ref "U2") (pin "P2") (pinfunction "VDDQ_P2") (pintype "power_in"))
      (node (ref "U2") (pin "P7") (pinfunction "VDDQ_P7") (pintype "power_in"))
      (node (ref "U2") (pin "R7") (pinfunction "VDD_R7") (pintype "power_in"))
    )
    (net (code "77") (name "unconnected-(J14-Pad1)") (class "Default")
      (node (ref "J14") (pin "1") (pinfunction "1_1") (pintype "passive+no_connect"))
    )
    (net (code "78") (name "unconnected-(RA19-Pad4)") (class "Default")
      (node (ref "RA19") (pin "4") (pinfunction "4_4") (pintype "passive+no_connect"))
    )
    (net (code "79") (name "unconnected-(RA19-Pad5)") (class "Default")
      (node (ref "RA19") (pin "5") (pinfunction "5_5") (pintype "passive+no_connect"))
    )
    (net (code "80") (name "unconnected-(U2B-NC-PadE3)") (class "Default")
      (node (ref "U2") (pin "E3") (pinfunction "NC_E3") (pintype "passive+no_connect"))
    )
    (net (code "81") (name "unconnected-(U2B-NC-PadE7)") (class "Default")
      (node (ref "U2") (pin "E7") (pinfunction "NC_E7") (pintype "passive+no_connect"))
    )
    (net (code "82") (name "unconnected-(U2B-NC-PadH7)") (class "Default")
      (node (ref "U2") (pin "H7") (pinfunction "NC_H7") (pintype "passive+no_connect"))
    )
    (net (code "83") (name "unconnected-(U2B-NC-PadK2)") (class "Default")
      (node (ref "U2") (pin "K2") (pinfunction "NC_K2") (pintype "passive+no_connect"))
    )
    (net (code "84") (name "unconnected-(U2B-NC-PadK3)") (class "Default")
      (node (ref "U2") (pin "K3") (pinfunction "NC_K3") (pintype "passive+no_connect"))
    )
  )
)
